# 7_-H3_POWER.net
KiCad netlist of a schematic drawn in Altium Designer
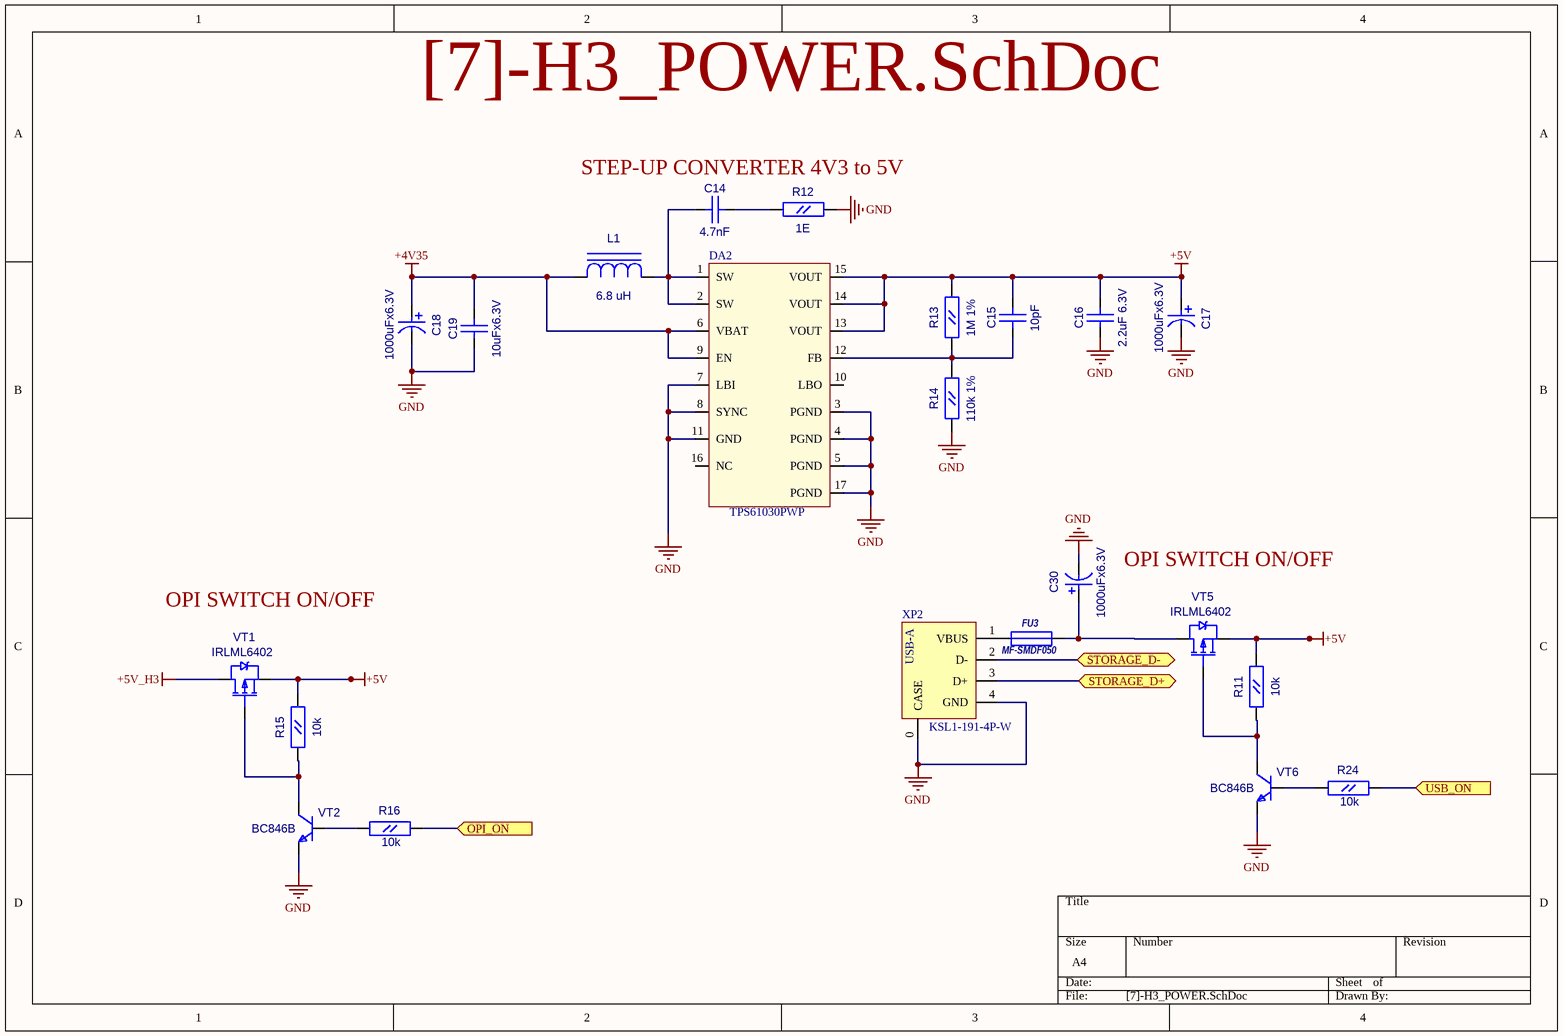
[diagram p0: [7]-H3_POWER.SchDoc]

(export (version "E")
  (design (tool "Eeschema 10.0.6"))
  (components
    (comp (ref "C14")
      (value "4.7nF")
      (footprint "CC0603")
      (description "CC0603")
      (libsource (lib "gprs_modem_2") (part "CC0603"))
    )
    (comp (ref "C15")
      (value "10pF")
      (footprint "CC0603")
      (description "CC0603")
      (libsource (lib "gprs_modem_2") (part "CC0603"))
    )
    (comp (ref "C16")
      (value "2.2uF 6.3V")
      (footprint "CC0805")
      (description "CC0805")
      (libsource (lib "gprs_modem_2") (part "CC0805"))
    )
    (comp (ref "C17")
      (value "1000uFx6.3V")
      (footprint "CC8X3.5")
      (description "CAP0.35")
      (libsource (lib "gprs_modem_2") (part "CAP0.35"))
    )
    (comp (ref "C18")
      (value "1000uFx6.3V")
      (footprint "CC8X3.5")
      (description "CAP0.35")
      (libsource (lib "gprs_modem_2") (part "CAP0.35"))
    )
    (comp (ref "C19")
      (value "10uFx6.3V")
      (footprint "CC0805")
      (description "CC0805")
      (libsource (lib "gprs_modem_2") (part "CC0805"))
    )
    (comp (ref "C30")
      (value "1000uFx6.3V")
      (footprint "CC8X3.5")
      (description "CAP0.35")
      (libsource (lib "gprs_modem_2") (part "CAP0.35"))
    )
    (comp (ref "DA2")
      (value "TPS61030PWP")
      (footprint "R-PDSO-G16")
      (description "Boost converter")
      (libsource (lib "gprs_modem") (part "TPS61030PWP"))
    )
    (comp (ref "FU3")
      (value "MF-SMDF050")
      (footprint "MF-SMDF")
      (description "MF-SMDF")
      (libsource (lib "fizik_lib") (part "MF-SMDF"))
    )
    (comp (ref "L1")
      (value "6.8 uH")
      (footprint "SDR0805")
      (description "SDR0805")
      (libsource (lib "gprs_modem_2") (part "SDR0805"))
    )
    (comp (ref "R11")
      (value "10k")
      (footprint "RC0603")
      (description "RC0603")
      (libsource (lib "gprs_modem_2") (part "RC0603"))
    )
    (comp (ref "R12")
      (value "1E")
      (footprint "RC0603")
      (description "RC0603")
      (libsource (lib "gprs_modem_2") (part "RC0603"))
    )
    (comp (ref "R13")
      (value "1M 1%")
      (footprint "RC0603")
      (description "RC0603")
      (libsource (lib "gprs_modem_2") (part "RC0603"))
    )
    (comp (ref "R14")
      (value "110k 1%")
      (footprint "RC0603")
      (description "RC0603")
      (libsource (lib "gprs_modem_2") (part "RC0603"))
    )
    (comp (ref "R15")
      (value "10k")
      (footprint "RC0603")
      (description "RC0603")
      (libsource (lib "gprs_modem_2") (part "RC0603"))
    )
    (comp (ref "R16")
      (value "10k")
      (footprint "RC0603")
      (description "RC0603")
      (libsource (lib "fizik_lib") (part "RC0603"))
    )
    (comp (ref "R24")
      (value "10k")
      (footprint "RC0603")
      (description "RC0603")
      (libsource (lib "fizik_lib") (part "RC0603"))
    )
    (comp (ref "VT1")
      (value "IRLML6402")
      (footprint "SOT-23(123)")
      (description "HEXFET Power MOSFET")
      (libsource (lib "gprs_modem_2") (part "IRLML6402"))
    )
    (comp (ref "VT2")
      (value "BC846B")
      (footprint "SOT-23(123)")
      (description "BC846BLT1")
      (libsource (lib "gprs_modem_2") (part "BC846BLT1"))
    )
    (comp (ref "VT5")
      (value "IRLML6402")
      (footprint "SOT-23(123)")
      (description "HEXFET Power MOSFET")
      (libsource (lib "gprs_modem_2") (part "IRLML6402"))
    )
    (comp (ref "VT6")
      (value "BC846B")
      (footprint "SOT-23(123)")
      (description "BC846BLT1")
      (libsource (lib "gprs_modem_2") (part "BC846BLT1"))
    )
    (comp (ref "XP2")
      (value "KSL1-191-4P-W")
      (footprint "USB_A_REAR")
      (description "USB A rear side connector")
      (libsource (lib "fizik_lib") (part "USB_A_REAR"))
    )
  )
  (nets
    (net (code "1") (name "+4V35") (class "Default")
      (node (ref "C18") (pin "1") (pintype "passive"))
      (node (ref "C19") (pin "2") (pinfunction "B_2") (pintype "passive"))
      (node (ref "DA2") (pin "6") (pinfunction "VBAT_6") (pintype "passive"))
      (node (ref "DA2") (pin "9") (pinfunction "EN_9") (pintype "passive"))
      (node (ref "L1") (pin "1") (pinfunction "C_1") (pintype "passive"))
    )
    (net (code "2") (name "+5V") (class "Default")
      (node (ref "C15") (pin "2") (pinfunction "B_2") (pintype "passive"))
      (node (ref "C16") (pin "2") (pinfunction "B_2") (pintype "passive"))
      (node (ref "C17") (pin "1") (pintype "passive"))
      (node (ref "DA2") (pin "13") (pinfunction "VOUT_13") (pintype "passive"))
      (node (ref "DA2") (pin "14") (pinfunction "VOUT_14") (pintype "passive"))
      (node (ref "DA2") (pin "15") (pinfunction "VOUT_15") (pintype "passive"))
      (node (ref "R11") (pin "2") (pinfunction "B_2") (pintype "passive"))
      (node (ref "R13") (pin "2") (pinfunction "B_2") (pintype "passive"))
      (node (ref "R15") (pin "2") (pinfunction "B_2") (pintype "passive"))
      (node (ref "VT1") (pin "2") (pinfunction "S_2") (pintype "passive"))
      (node (ref "VT5") (pin "2") (pinfunction "S_2") (pintype "passive"))
    )
    (net (code "3") (name "+5V_H3") (class "Default")
      (node (ref "VT1") (pin "3") (pinfunction "D_3") (pintype "passive"))
    )
    (net (code "4") (name "/OPI_ON") (class "Default")
      (node (ref "R16") (pin "2") (pinfunction "B_2") (pintype "passive"))
    )
    (net (code "5") (name "/STORAGE_D+") (class "Default")
      (node (ref "XP2") (pin "3") (pinfunction "D+_3") (pintype "passive"))
    )
    (net (code "6") (name "/STORAGE_D-") (class "Default")
      (node (ref "XP2") (pin "2") (pinfunction "D-_2") (pintype "passive"))
    )
    (net (code "7") (name "/USB_ON") (class "Default")
      (node (ref "R24") (pin "2") (pinfunction "B_2") (pintype "passive"))
    )
    (net (code "8") (name "GND") (class "Default")
      (node (ref "C16") (pin "1") (pinfunction "A_1") (pintype "passive"))
      (node (ref "C17") (pin "2") (pintype "passive"))
      (node (ref "C18") (pin "2") (pintype "passive"))
      (node (ref "C19") (pin "1") (pinfunction "A_1") (pintype "passive"))
      (node (ref "C30") (pin "2") (pintype "passive"))
      (node (ref "DA2") (pin "11") (pinfunction "GND_11") (pintype "passive"))
      (node (ref "DA2") (pin "17") (pinfunction "PGND_17") (pintype "passive"))
      (node (ref "DA2") (pin "3") (pinfunction "PGND_3") (pintype "passive"))
      (node (ref "DA2") (pin "4") (pinfunction "PGND_4") (pintype "passive"))
      (node (ref "DA2") (pin "5") (pinfunction "PGND_5") (pintype "passive"))
      (node (ref "DA2") (pin "7") (pinfunction "LBI_7") (pintype "passive"))
      (node (ref "DA2") (pin "8") (pinfunction "SYNC_8") (pintype "passive"))
      (node (ref "R12") (pin "2") (pinfunction "B_2") (pintype "passive"))
      (node (ref "R14") (pin "1") (pinfunction "A_1") (pintype "passive"))
      (node (ref "VT2") (pin "2") (pinfunction "E_2") (pintype "passive"))
      (node (ref "VT6") (pin "2") (pinfunction "E_2") (pintype "passive"))
      (node (ref "XP2") (pin "0") (pinfunction "CASE_0") (pintype "passive"))
      (node (ref "XP2") (pin "4") (pinfunction "GND_4") (pintype "passive"))
    )
    (net (code "9") (name "Net-(C14-A)") (class "Default")
      (node (ref "C14") (pin "1") (pinfunction "A_1") (pintype "passive"))
      (node (ref "DA2") (pin "1") (pinfunction "SW_1") (pintype "passive"))
      (node (ref "DA2") (pin "2") (pinfunction "SW_2") (pintype "passive"))
      (node (ref "L1") (pin "2") (pinfunction "A_2") (pintype "passive"))
    )
    (net (code "10") (name "Net-(C14-B)") (class "Default")
      (node (ref "C14") (pin "2") (pinfunction "B_2") (pintype "passive"))
      (node (ref "R12") (pin "1") (pinfunction "A_1") (pintype "passive"))
    )
    (net (code "11") (name "Net-(C15-A)") (class "Default")
      (node (ref "C15") (pin "1") (pinfunction "A_1") (pintype "passive"))
      (node (ref "DA2") (pin "12") (pinfunction "FB_12") (pintype "passive"))
      (node (ref "R13") (pin "1") (pinfunction "A_1") (pintype "passive"))
      (node (ref "R14") (pin "2") (pinfunction "B_2") (pintype "passive"))
    )
    (net (code "12") (name "Net-(R11-A)") (class "Default")
      (node (ref "R11") (pin "1") (pinfunction "A_1") (pintype "passive"))
      (node (ref "VT5") (pin "1") (pinfunction "G_1") (pintype "passive"))
      (node (ref "VT6") (pin "3") (pinfunction "C_3") (pintype "passive"))
    )
    (net (code "13") (name "Net-(R15-A)") (class "Default")
      (node (ref "R15") (pin "1") (pinfunction "A_1") (pintype "passive"))
      (node (ref "VT1") (pin "1") (pinfunction "G_1") (pintype "passive"))
      (node (ref "VT2") (pin "3") (pinfunction "C_3") (pintype "passive"))
    )
    (net (code "14") (name "Net-(R16-A)") (class "Default")
      (node (ref "R16") (pin "1") (pinfunction "A_1") (pintype "passive"))
      (node (ref "VT2") (pin "1") (pinfunction "B_1") (pintype "passive"))
    )
    (net (code "15") (name "Net-(R24-A)") (class "Default")
      (node (ref "R24") (pin "1") (pinfunction "A_1") (pintype "passive"))
      (node (ref "VT6") (pin "1") (pinfunction "B_1") (pintype "passive"))
    )
    (net (code "16") (name "Net-(VT5-D)") (class "Default")
      (node (ref "C30") (pin "1") (pintype "passive"))
      (node (ref "FU3") (pin "2") (pintype "passive"))
      (node (ref "VT5") (pin "3") (pinfunction "D_3") (pintype "passive"))
    )
    (net (code "17") (name "Net-(XP2-VBUS)") (class "Default")
      (node (ref "FU3") (pin "1") (pintype "passive"))
      (node (ref "XP2") (pin "1") (pinfunction "VBUS_1") (pintype "passive"))
    )
    (net (code "18") (name "unconnected-(DA2-LBO-Pad10)") (class "Default")
      (node (ref "DA2") (pin "10") (pinfunction "LBO_10") (pintype "passive"))
    )
    (net (code "19") (name "unconnected-(DA2-NC-Pad16)") (class "Default")
      (node (ref "DA2") (pin "16") (pinfunction "NC_16") (pintype "passive"))
    )
  )
)
